# NCV7708_-_6_SILNKOW_2021-04-09.net
KiCad netlist of a schematic drawn in EasyEDA
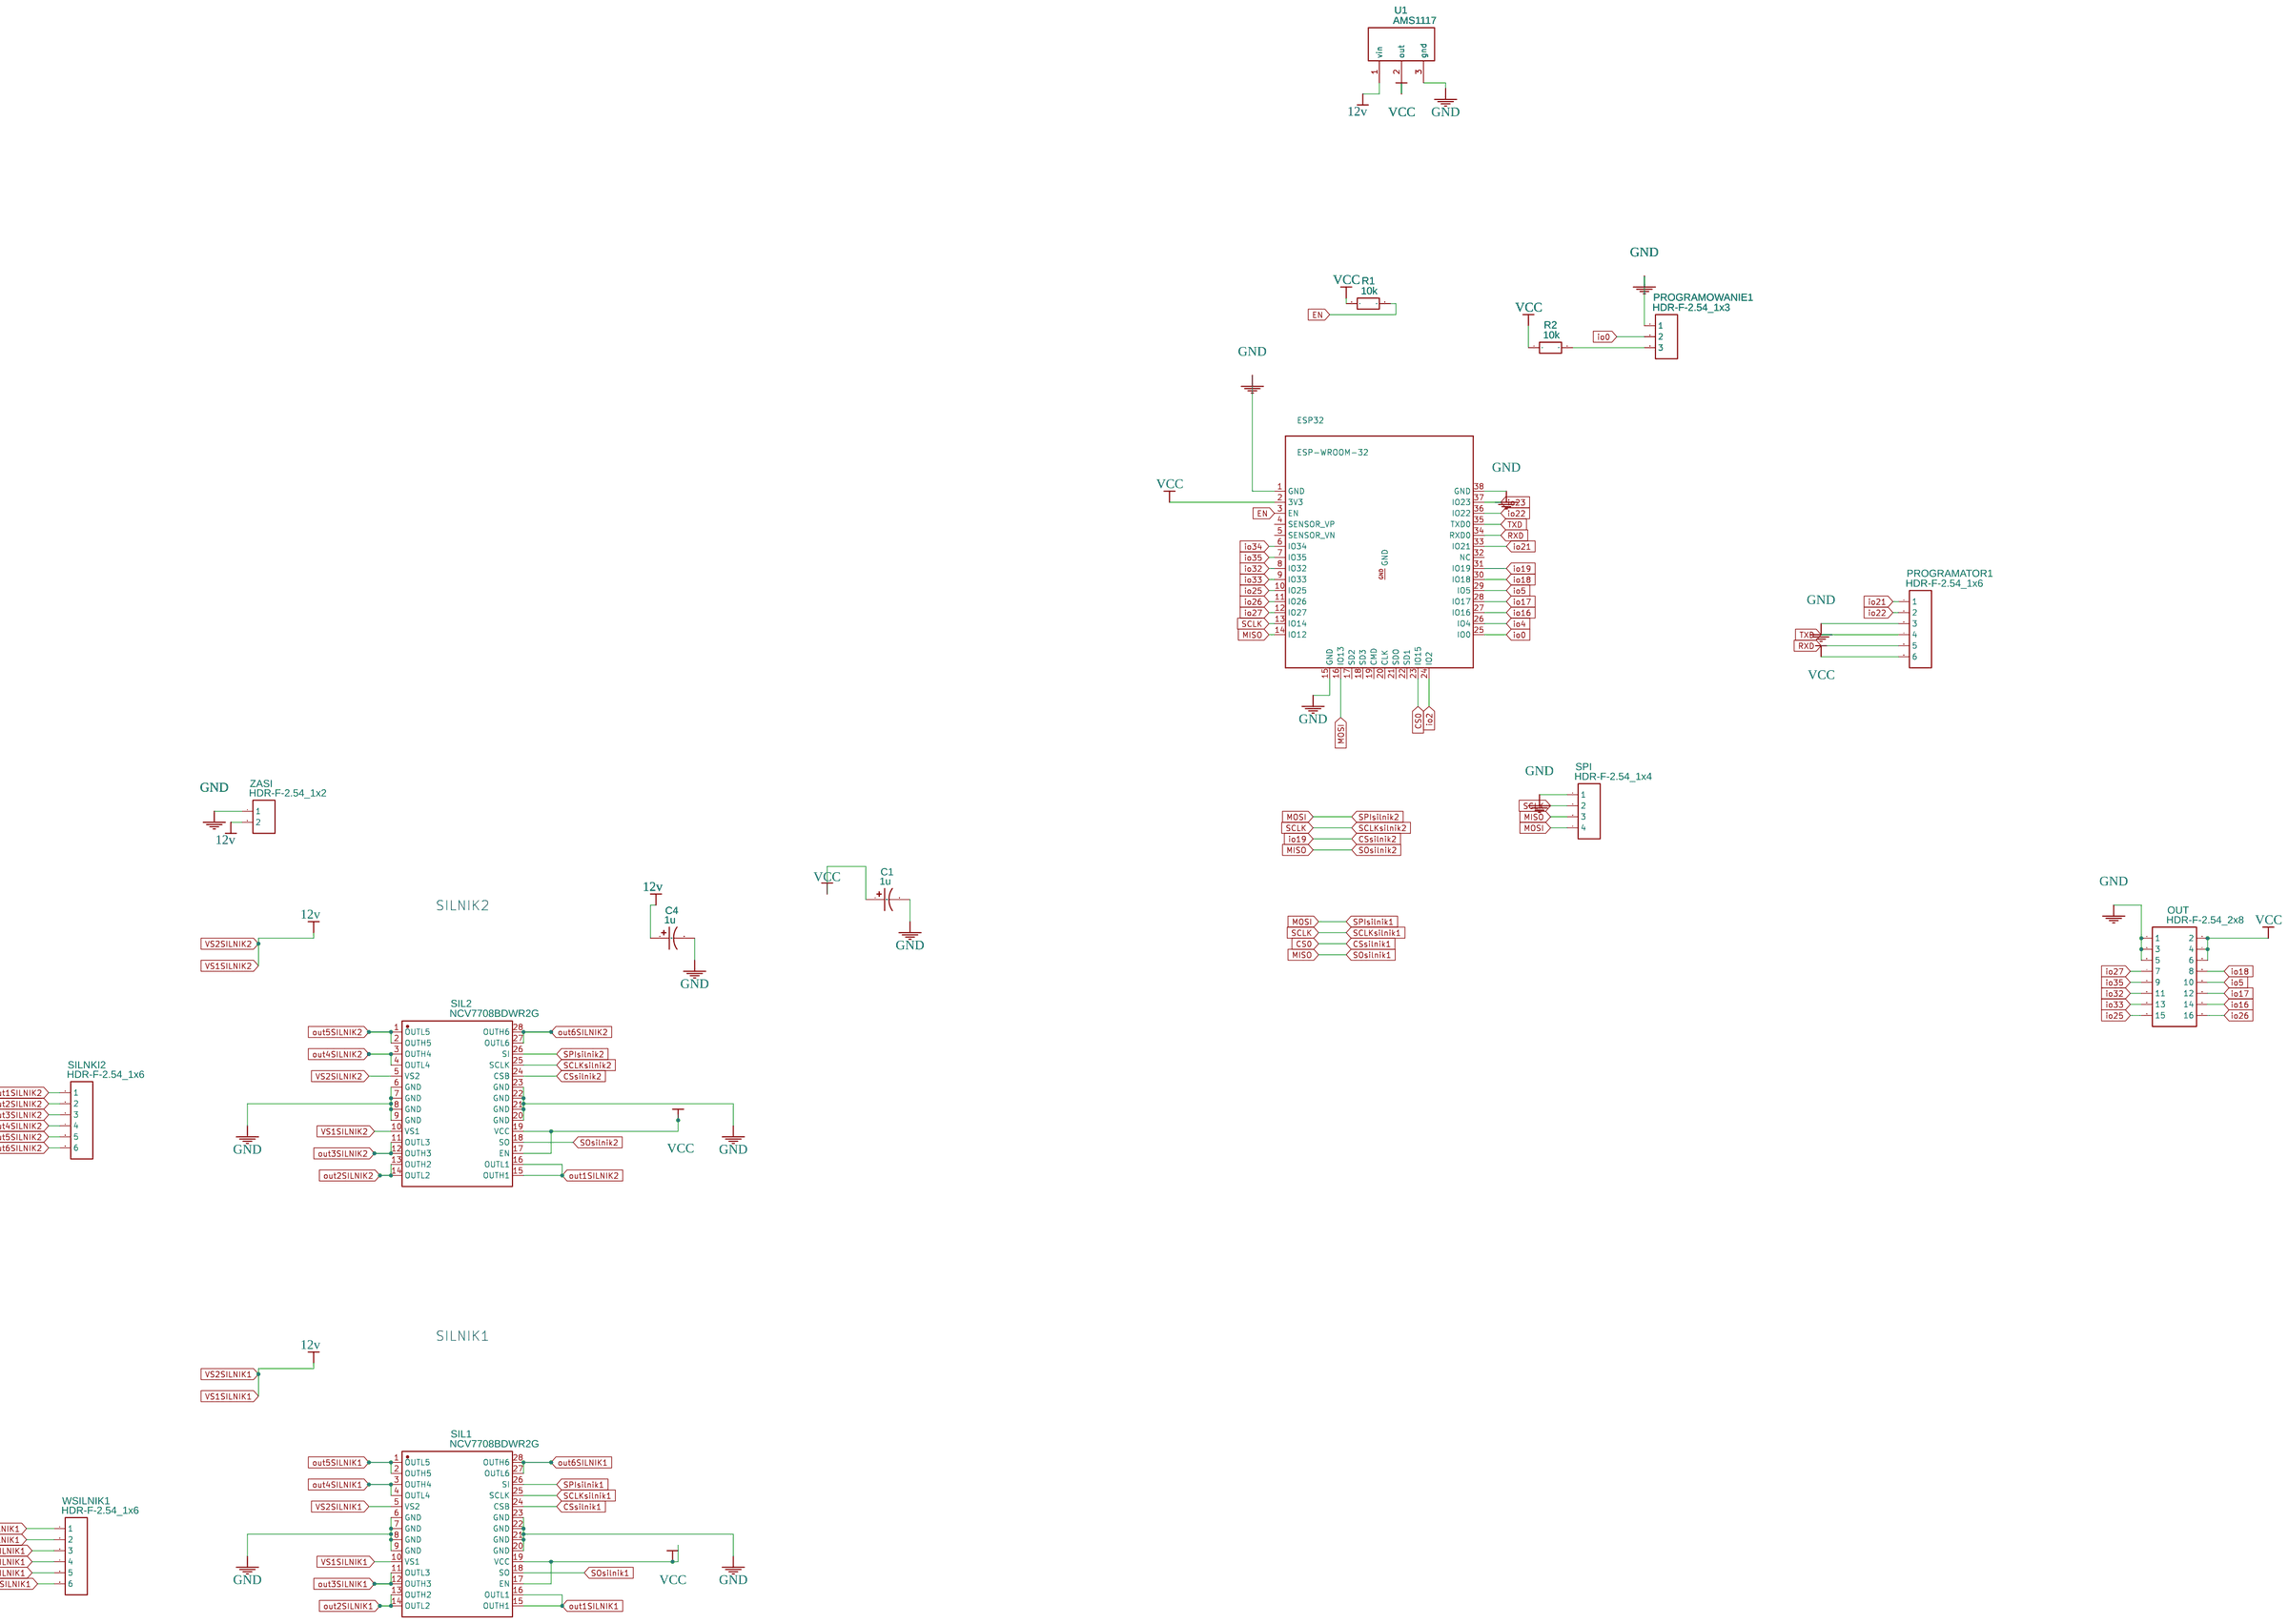
[diagram p0: schematic sheet]

(export (version "E")
  (design (tool "Eeschema 10.0.6"))
  (components
    (comp (ref "C1") (value "1u") (libsource (lib "") (part "CE_TH_D4.0×F1.5_US")))
    (comp (ref "C4") (value "1u") (libsource (lib "") (part "CE_TH_D4.0×F1.5_US")))
    (comp (ref "ESP32")
      (value "ESP-WROOM-32")
      (fields (field (name "BOM_Supplier Part") "undefined"))
      (libsource (lib "") (part "Unknown_1320_-1500"))
    )
    (comp (ref "OUT")
      (value "HDR-F-2.54_2x8")
      (fields (field (name "BOM_Supplier Part") "C30734"))
      (libsource (lib "") (part "HDR-F-2.54_2x8"))
    )
    (comp (ref "PROGRAMATOR1")
      (value "HDR-F-2.54_1x6")
      (fields (field (name "BOM_Supplier Part") "C40877"))
      (libsource (lib "") (part "HDR-F-2.54_1x6_2"))
    )
    (comp (ref "PROGRAMOWANIE1")
      (value "HDR-F-2.54_1x3")
      (fields (field (name "BOM_Supplier Part") "C146690"))
      (libsource (lib "") (part "HDR-F-2.54_1x3"))
    )
    (comp (ref "R1") (value "10k") (libsource (lib "") (part "R_0805_EU")))
    (comp (ref "R2") (value "10k") (libsource (lib "") (part "R_0805_EU")))
    (comp (ref "SIL1")
      (value "NCV7708BDWR2G")
      (fields (field (name "BOM_Supplier Part") "C70892"))
      (libsource (lib "") (part "NCV7708BDWR2G"))
    )
    (comp (ref "SIL2")
      (value "NCV7708BDWR2G")
      (fields (field (name "BOM_Supplier Part") "C70892"))
      (libsource (lib "") (part "NCV7708BDWR2G"))
    )
    (comp (ref "SILNKI2")
      (value "HDR-F-2.54_1x6")
      (fields (field (name "BOM_Supplier Part") "C40877"))
      (libsource (lib "") (part "HDR-F-2.54_1x6_1"))
    )
    (comp (ref "SPI")
      (value "HDR-F-2.54_1x4")
      (fields (field (name "BOM_Supplier Part") "C225501"))
      (libsource (lib "") (part "HDR-F-2.54_1x4"))
    )
    (comp (ref "U1") (value "AMS1117") (libsource (lib "") (part "AMS1117")))
    (comp (ref "WSILNIK1")
      (value "HDR-F-2.54_1x6")
      (fields (field (name "BOM_Supplier Part") "C40877"))
      (libsource (lib "") (part "HDR-F-2.54_1x6"))
    )
    (comp (ref "ZASI")
      (value "HDR-F-2.54_1x2")
      (fields (field (name "BOM_Supplier Part") "C49661"))
      (libsource (lib "") (part "HDR-F-2.54_1x2"))
    )
  )
  (nets
    (net (code "1") (name "CS0") (class "Default")
      (node (ref "ESP32") (pin "23") (pinfunction "IO15_23") (pintype "bidirectional"))
      (node (ref "SIL1") (pin "24") (pinfunction "CSB_24") (pintype "unspecified"))
    )
    (net (code "2") (name "CSsilnik2") (class "Default")
      (node (ref "ESP32") (pin "31") (pinfunction "IO19_31") (pintype "bidirectional"))
      (node (ref "SIL2") (pin "24") (pinfunction "CSB_24") (pintype "unspecified"))
    )
    (net (code "3") (name "EN") (class "Default")
      (node (ref "ESP32") (pin "3") (pinfunction "EN_3") (pintype "bidirectional"))
      (node (ref "R1") (pin "2") (pinfunction "2_2") (pintype "unspecified"))
    )
    (net (code "4") (name "GND") (class "Default")
      (node (ref "C1") (pin "2") (pinfunction "2_2") (pintype "unspecified"))
      (node (ref "C4") (pin "2") (pinfunction "2_2") (pintype "unspecified"))
      (node (ref "ESP32") (pin "1") (pinfunction "GND_1") (pintype "passive"))
      (node (ref "ESP32") (pin "15") (pinfunction "GND_15") (pintype "bidirectional"))
      (node (ref "ESP32") (pin "38") (pinfunction "GND_38") (pintype "bidirectional"))
      (node (ref "OUT") (pin "1") (pinfunction "1_1") (pintype "input"))
      (node (ref "OUT") (pin "3") (pinfunction "3_3") (pintype "input"))
      (node (ref "OUT") (pin "5") (pinfunction "5_5") (pintype "input"))
      (node (ref "PROGRAMATOR1") (pin "3") (pinfunction "3_3") (pintype "input"))
      (node (ref "PROGRAMOWANIE1") (pin "1") (pinfunction "1_1") (pintype "input"))
      (node (ref "SIL1") (pin "20") (pinfunction "GND_20") (pintype "unspecified"))
      (node (ref "SIL1") (pin "21") (pinfunction "GND_21") (pintype "unspecified"))
      (node (ref "SIL1") (pin "22") (pinfunction "GND_22") (pintype "unspecified"))
      (node (ref "SIL1") (pin "23") (pinfunction "GND_23") (pintype "unspecified"))
      (node (ref "SIL1") (pin "6") (pinfunction "GND_6") (pintype "unspecified"))
      (node (ref "SIL1") (pin "7") (pinfunction "GND_7") (pintype "unspecified"))
      (node (ref "SIL1") (pin "8") (pinfunction "GND_8") (pintype "unspecified"))
      (node (ref "SIL1") (pin "9") (pinfunction "GND_9") (pintype "unspecified"))
      (node (ref "SIL2") (pin "20") (pinfunction "GND_20") (pintype "unspecified"))
      (node (ref "SIL2") (pin "21") (pinfunction "GND_21") (pintype "unspecified"))
      (node (ref "SIL2") (pin "22") (pinfunction "GND_22") (pintype "unspecified"))
      (node (ref "SIL2") (pin "23") (pinfunction "GND_23") (pintype "unspecified"))
      (node (ref "SIL2") (pin "6") (pinfunction "GND_6") (pintype "unspecified"))
      (node (ref "SIL2") (pin "7") (pinfunction "GND_7") (pintype "unspecified"))
      (node (ref "SIL2") (pin "8") (pinfunction "GND_8") (pintype "unspecified"))
      (node (ref "SIL2") (pin "9") (pinfunction "GND_9") (pintype "unspecified"))
      (node (ref "SPI") (pin "1") (pinfunction "1_1") (pintype "unspecified"))
      (node (ref "U1") (pin "3") (pinfunction "gnd_3") (pintype "unspecified"))
      (node (ref "ZASI") (pin "1") (pinfunction "1_1") (pintype "input"))
    )
    (net (code "5") (name "MISO") (class "Default")
      (node (ref "ESP32") (pin "14") (pinfunction "IO12_14") (pintype "bidirectional"))
      (node (ref "SIL1") (pin "18") (pinfunction "SO_18") (pintype "unspecified"))
      (node (ref "SIL2") (pin "18") (pinfunction "SO_18") (pintype "unspecified"))
      (node (ref "SPI") (pin "3") (pinfunction "3_3") (pintype "unspecified"))
    )
    (net (code "6") (name "MOSI") (class "Default")
      (node (ref "ESP32") (pin "16") (pinfunction "IO13_16") (pintype "bidirectional"))
      (node (ref "SIL1") (pin "26") (pinfunction "SI_26") (pintype "unspecified"))
      (node (ref "SIL2") (pin "26") (pinfunction "SI_26") (pintype "unspecified"))
      (node (ref "SPI") (pin "4") (pinfunction "4_4") (pintype "unspecified"))
    )
    (net (code "7") (name "Net-(PROGRAMOWANIE1-Pad3)") (class "Default")
      (node (ref "PROGRAMOWANIE1") (pin "3") (pinfunction "3_3") (pintype "input"))
      (node (ref "R2") (pin "2") (pinfunction "2_2") (pintype "unspecified"))
    )
    (net (code "8") (name "RXD") (class "Default")
      (node (ref "ESP32") (pin "34") (pinfunction "RXD0_34") (pintype "bidirectional"))
      (node (ref "PROGRAMATOR1") (pin "5") (pinfunction "5_5") (pintype "input"))
    )
    (net (code "9") (name "SCLK") (class "Default")
      (node (ref "ESP32") (pin "13") (pinfunction "IO14_13") (pintype "bidirectional"))
      (node (ref "SIL1") (pin "25") (pinfunction "SCLK_25") (pintype "unspecified"))
      (node (ref "SIL2") (pin "25") (pinfunction "SCLK_25") (pintype "unspecified"))
      (node (ref "SPI") (pin "2") (pinfunction "2_2") (pintype "unspecified"))
    )
    (net (code "10") (name "TXD") (class "Default")
      (node (ref "ESP32") (pin "35") (pinfunction "TXD0_35") (pintype "bidirectional"))
      (node (ref "PROGRAMATOR1") (pin "4") (pinfunction "4_4") (pintype "input"))
    )
    (net (code "11") (name "VCC") (class "Default")
      (node (ref "C1") (pin "1") (pinfunction "1_1") (pintype "unspecified"))
      (node (ref "ESP32") (pin "2") (pinfunction "3V3_2") (pintype "passive"))
      (node (ref "OUT") (pin "2") (pinfunction "2_2") (pintype "input"))
      (node (ref "OUT") (pin "4") (pinfunction "4_4") (pintype "input"))
      (node (ref "OUT") (pin "6") (pinfunction "6_6") (pintype "input"))
      (node (ref "PROGRAMATOR1") (pin "6") (pinfunction "6_6") (pintype "input"))
      (node (ref "R1") (pin "1") (pinfunction "1_1") (pintype "unspecified"))
      (node (ref "R2") (pin "1") (pinfunction "1_1") (pintype "unspecified"))
      (node (ref "SIL1") (pin "17") (pinfunction "EN_17") (pintype "unspecified"))
      (node (ref "SIL1") (pin "19") (pinfunction "VCC_19") (pintype "unspecified"))
      (node (ref "SIL2") (pin "17") (pinfunction "EN_17") (pintype "unspecified"))
      (node (ref "SIL2") (pin "19") (pinfunction "VCC_19") (pintype "unspecified"))
      (node (ref "U1") (pin "2") (pinfunction "out_2") (pintype "unspecified"))
    )
    (net (code "12") (name "VS1SILNIK1") (class "Default")
      (node (ref "C4") (pin "1") (pinfunction "1_1") (pintype "unspecified"))
      (node (ref "SIL1") (pin "10") (pinfunction "VS1_10") (pintype "unspecified"))
      (node (ref "SIL1") (pin "5") (pinfunction "VS2_5") (pintype "unspecified"))
      (node (ref "SIL2") (pin "10") (pinfunction "VS1_10") (pintype "unspecified"))
      (node (ref "SIL2") (pin "5") (pinfunction "VS2_5") (pintype "unspecified"))
      (node (ref "U1") (pin "1") (pinfunction "vin_1") (pintype "unspecified"))
      (node (ref "ZASI") (pin "2") (pinfunction "2_2") (pintype "input"))
    )
    (net (code "13") (name "io0") (class "Default")
      (node (ref "ESP32") (pin "25") (pinfunction "IO0_25") (pintype "bidirectional"))
      (node (ref "PROGRAMOWANIE1") (pin "2") (pinfunction "2_2") (pintype "input"))
    )
    (net (code "14") (name "io2") (class "Default")
      (node (ref "ESP32") (pin "24") (pinfunction "IO2_24") (pintype "bidirectional"))
    )
    (net (code "15") (name "io4") (class "Default")
      (node (ref "ESP32") (pin "26") (pinfunction "IO4_26") (pintype "bidirectional"))
    )
    (net (code "16") (name "io5") (class "Default")
      (node (ref "ESP32") (pin "29") (pinfunction "IO5_29") (pintype "bidirectional"))
      (node (ref "OUT") (pin "10") (pinfunction "10_10") (pintype "input"))
    )
    (net (code "17") (name "io16") (class "Default")
      (node (ref "ESP32") (pin "27") (pinfunction "IO16_27") (pintype "bidirectional"))
      (node (ref "OUT") (pin "14") (pinfunction "14_14") (pintype "input"))
    )
    (net (code "18") (name "io17") (class "Default")
      (node (ref "ESP32") (pin "28") (pinfunction "IO17_28") (pintype "bidirectional"))
      (node (ref "OUT") (pin "12") (pinfunction "12_12") (pintype "input"))
    )
    (net (code "19") (name "io18") (class "Default")
      (node (ref "ESP32") (pin "30") (pinfunction "IO18_30") (pintype "bidirectional"))
      (node (ref "OUT") (pin "8") (pinfunction "8_8") (pintype "input"))
    )
    (net (code "20") (name "io21") (class "Default")
      (node (ref "ESP32") (pin "33") (pinfunction "IO21_33") (pintype "bidirectional"))
      (node (ref "PROGRAMATOR1") (pin "1") (pinfunction "1_1") (pintype "input"))
    )
    (net (code "21") (name "io22") (class "Default")
      (node (ref "ESP32") (pin "36") (pinfunction "IO22_36") (pintype "bidirectional"))
      (node (ref "PROGRAMATOR1") (pin "2") (pinfunction "2_2") (pintype "input"))
    )
    (net (code "22") (name "io23") (class "Default")
      (node (ref "ESP32") (pin "37") (pinfunction "IO23_37") (pintype "bidirectional"))
    )
    (net (code "23") (name "io25") (class "Default")
      (node (ref "ESP32") (pin "10") (pinfunction "IO25_10") (pintype "bidirectional"))
      (node (ref "OUT") (pin "15") (pinfunction "15_15") (pintype "input"))
    )
    (net (code "24") (name "io26") (class "Default")
      (node (ref "ESP32") (pin "11") (pinfunction "IO26_11") (pintype "bidirectional"))
      (node (ref "OUT") (pin "16") (pinfunction "16_16") (pintype "input"))
    )
    (net (code "25") (name "io27") (class "Default")
      (node (ref "ESP32") (pin "12") (pinfunction "IO27_12") (pintype "bidirectional"))
      (node (ref "OUT") (pin "7") (pinfunction "7_7") (pintype "input"))
    )
    (net (code "26") (name "io32") (class "Default")
      (node (ref "ESP32") (pin "8") (pinfunction "IO32_8") (pintype "bidirectional"))
      (node (ref "OUT") (pin "11") (pinfunction "11_11") (pintype "input"))
    )
    (net (code "27") (name "io33") (class "Default")
      (node (ref "ESP32") (pin "9") (pinfunction "IO33_9") (pintype "bidirectional"))
      (node (ref "OUT") (pin "13") (pinfunction "13_13") (pintype "input"))
    )
    (net (code "28") (name "io34") (class "Default")
      (node (ref "ESP32") (pin "6") (pinfunction "IO34_6") (pintype "bidirectional"))
    )
    (net (code "29") (name "io35") (class "Default")
      (node (ref "ESP32") (pin "7") (pinfunction "IO35_7") (pintype "bidirectional"))
      (node (ref "OUT") (pin "9") (pinfunction "9_9") (pintype "input"))
    )
    (net (code "30") (name "out1SILNIK1") (class "Default")
      (node (ref "SIL1") (pin "15") (pinfunction "OUTH1_15") (pintype "unspecified"))
      (node (ref "SIL1") (pin "16") (pinfunction "OUTL1_16") (pintype "unspecified"))
      (node (ref "WSILNIK1") (pin "1") (pinfunction "1_1") (pintype "input"))
    )
    (net (code "31") (name "out1SILNIK2") (class "Default")
      (node (ref "SIL2") (pin "15") (pinfunction "OUTH1_15") (pintype "unspecified"))
      (node (ref "SIL2") (pin "16") (pinfunction "OUTL1_16") (pintype "unspecified"))
      (node (ref "SILNKI2") (pin "1") (pinfunction "1_1") (pintype "input"))
    )
    (net (code "32") (name "out2SILNIK1") (class "Default")
      (node (ref "SIL1") (pin "13") (pinfunction "OUTH2_13") (pintype "unspecified"))
      (node (ref "SIL1") (pin "14") (pinfunction "OUTL2_14") (pintype "unspecified"))
      (node (ref "WSILNIK1") (pin "2") (pinfunction "2_2") (pintype "input"))
    )
    (net (code "33") (name "out2SILNIK2") (class "Default")
      (node (ref "SIL2") (pin "13") (pinfunction "OUTH2_13") (pintype "unspecified"))
      (node (ref "SIL2") (pin "14") (pinfunction "OUTL2_14") (pintype "unspecified"))
      (node (ref "SILNKI2") (pin "2") (pinfunction "2_2") (pintype "input"))
    )
    (net (code "34") (name "out3SILNIK1") (class "Default")
      (node (ref "SIL1") (pin "11") (pinfunction "OUTL3_11") (pintype "unspecified"))
      (node (ref "SIL1") (pin "12") (pinfunction "OUTH3_12") (pintype "unspecified"))
      (node (ref "WSILNIK1") (pin "3") (pinfunction "3_3") (pintype "input"))
    )
    (net (code "35") (name "out3SILNIK2") (class "Default")
      (node (ref "SIL2") (pin "11") (pinfunction "OUTL3_11") (pintype "unspecified"))
      (node (ref "SIL2") (pin "12") (pinfunction "OUTH3_12") (pintype "unspecified"))
      (node (ref "SILNKI2") (pin "3") (pinfunction "3_3") (pintype "input"))
    )
    (net (code "36") (name "out4SILNIK1") (class "Default")
      (node (ref "SIL1") (pin "3") (pinfunction "OUTH4_3") (pintype "unspecified"))
      (node (ref "SIL1") (pin "4") (pinfunction "OUTL4_4") (pintype "unspecified"))
      (node (ref "WSILNIK1") (pin "4") (pinfunction "4_4") (pintype "input"))
    )
    (net (code "37") (name "out4SILNIK2") (class "Default")
      (node (ref "SIL2") (pin "3") (pinfunction "OUTH4_3") (pintype "unspecified"))
      (node (ref "SIL2") (pin "4") (pinfunction "OUTL4_4") (pintype "unspecified"))
      (node (ref "SILNKI2") (pin "4") (pinfunction "4_4") (pintype "input"))
    )
    (net (code "38") (name "out5SILNIK1") (class "Default")
      (node (ref "SIL1") (pin "1") (pinfunction "OUTL5_1") (pintype "unspecified"))
      (node (ref "SIL1") (pin "2") (pinfunction "OUTH5_2") (pintype "unspecified"))
      (node (ref "WSILNIK1") (pin "5") (pinfunction "5_5") (pintype "input"))
    )
    (net (code "39") (name "out5SILNIK2") (class "Default")
      (node (ref "SIL2") (pin "1") (pinfunction "OUTL5_1") (pintype "unspecified"))
      (node (ref "SIL2") (pin "2") (pinfunction "OUTH5_2") (pintype "unspecified"))
      (node (ref "SILNKI2") (pin "5") (pinfunction "5_5") (pintype "input"))
    )
    (net (code "40") (name "out6SILNIK1") (class "Default")
      (node (ref "SIL1") (pin "27") (pinfunction "OUTL6_27") (pintype "unspecified"))
      (node (ref "SIL1") (pin "28") (pinfunction "OUTH6_28") (pintype "unspecified"))
      (node (ref "WSILNIK1") (pin "6") (pinfunction "6_6") (pintype "input"))
    )
    (net (code "41") (name "out6SILNIK2") (class "Default")
      (node (ref "SIL2") (pin "27") (pinfunction "OUTL6_27") (pintype "unspecified"))
      (node (ref "SIL2") (pin "28") (pinfunction "OUTH6_28") (pintype "unspecified"))
      (node (ref "SILNKI2") (pin "6") (pinfunction "6_6") (pintype "input"))
    )
    (net (code "42") (name "unconnected-(ESP32-CLK-Pad20)") (class "Default")
      (node (ref "ESP32") (pin "20") (pinfunction "CLK_20") (pintype "bidirectional"))
    )
    (net (code "43") (name "unconnected-(ESP32-CMD-Pad19)") (class "Default")
      (node (ref "ESP32") (pin "19") (pinfunction "CMD_19") (pintype "bidirectional"))
    )
    (net (code "44") (name "unconnected-(ESP32-NC-Pad32)") (class "Default")
      (node (ref "ESP32") (pin "32") (pinfunction "NC_32") (pintype "bidirectional"))
    )
    (net (code "45") (name "unconnected-(ESP32-PadGND)") (class "Default")
      (node (ref "ESP32") (pin "GND") (pinfunction "GND_GND") (pintype "passive"))
    )
    (net (code "46") (name "unconnected-(ESP32-SD1-Pad22)") (class "Default")
      (node (ref "ESP32") (pin "22") (pinfunction "SD1_22") (pintype "bidirectional"))
    )
    (net (code "47") (name "unconnected-(ESP32-SD2-Pad17)") (class "Default")
      (node (ref "ESP32") (pin "17") (pinfunction "SD2_17") (pintype "bidirectional"))
    )
    (net (code "48") (name "unconnected-(ESP32-SD3-Pad18)") (class "Default")
      (node (ref "ESP32") (pin "18") (pinfunction "SD3_18") (pintype "bidirectional"))
    )
    (net (code "49") (name "unconnected-(ESP32-SDO-Pad21)") (class "Default")
      (node (ref "ESP32") (pin "21") (pinfunction "SDO_21") (pintype "bidirectional"))
    )
    (net (code "50") (name "unconnected-(ESP32-SENSOR_VN-Pad5)") (class "Default")
      (node (ref "ESP32") (pin "5") (pinfunction "SENSOR_VN_5") (pintype "bidirectional"))
    )
    (net (code "51") (name "unconnected-(ESP32-SENSOR_VP-Pad4)") (class "Default")
      (node (ref "ESP32") (pin "4") (pinfunction "SENSOR_VP_4") (pintype "bidirectional"))
    )
  )
)
